# main.net
KiCad netlist of a schematic drawn in EAGLE
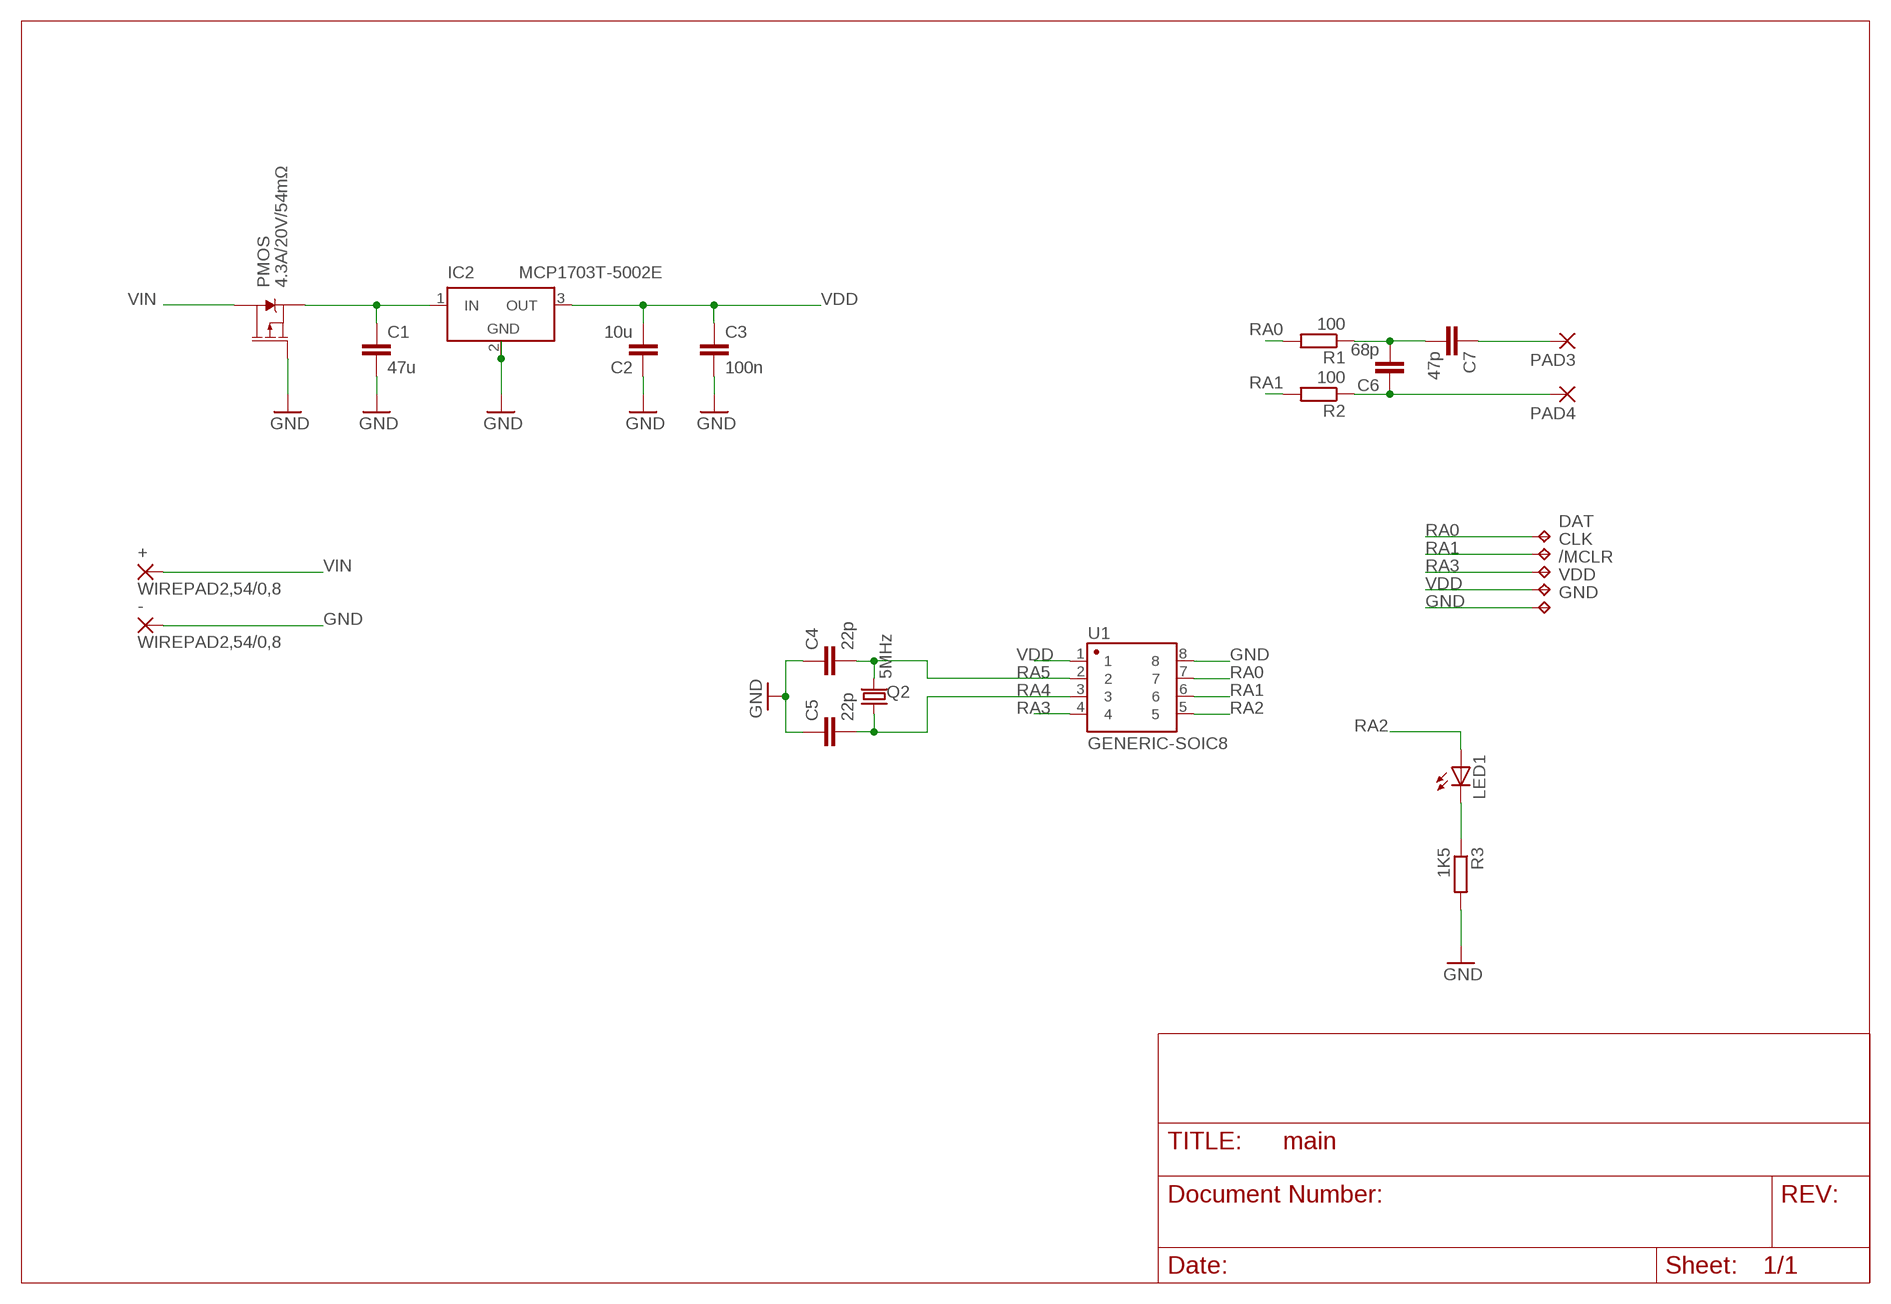
[diagram p0: schematic, sheet 1]

(export (version "E")
  (design (tool "Eeschema 10.0.6"))
  (components
    (comp (ref "+")
      (value "WIREPAD2,54/0,8")
      (footprint "eagle-import:2,54_0,8")
      (libsource (lib "eagle-import") (part "WIREPAD2,54/0,8"))
    )
    (comp (ref "-")
      (value "WIREPAD2,54/0,8")
      (footprint "eagle-import:2,54_0,8")
      (libsource (lib "eagle-import") (part "WIREPAD2,54/0,8"))
    )
    (comp (ref "/MCLR")
      (value "TPTP08SQ")
      (footprint "eagle-import:TP08SQ")
      (libsource (lib "eagle-import") (part "TPTP08SQ"))
    )
    (comp (ref "C1")
      (value "47u")
      (footprint "eagle-import:C1206")
      (libsource (lib "eagle-import") (part "C-EUC1206"))
    )
    (comp (ref "C2")
      (value "10u")
      (footprint "eagle-import:C1206")
      (libsource (lib "eagle-import") (part "C-EUC1206"))
    )
    (comp (ref "C3")
      (value "100n")
      (footprint "eagle-import:C0603")
      (libsource (lib "eagle-import") (part "C-EUC0603"))
    )
    (comp (ref "C4")
      (value "22p")
      (footprint "eagle-import:C0603")
      (libsource (lib "eagle-import") (part "C-EUC0603"))
    )
    (comp (ref "C5")
      (value "22p")
      (footprint "eagle-import:C0603")
      (libsource (lib "eagle-import") (part "C-EUC0603"))
    )
    (comp (ref "C6")
      (value "68p")
      (footprint "eagle-import:C0603")
      (libsource (lib "eagle-import") (part "C-EUC0603"))
    )
    (comp (ref "C7")
      (value "47p")
      (footprint "eagle-import:C0603")
      (libsource (lib "eagle-import") (part "C-EUC0603"))
    )
    (comp (ref "CLK")
      (value "TPTP08SQ")
      (footprint "eagle-import:TP08SQ")
      (libsource (lib "eagle-import") (part "TPTP08SQ"))
    )
    (comp (ref "DAT")
      (value "TPTP08SQ")
      (footprint "eagle-import:TP08SQ")
      (libsource (lib "eagle-import") (part "TPTP08SQ"))
    )
    (comp (ref "GND")
      (value "TPTP08SQ")
      (footprint "eagle-import:TP08SQ")
      (libsource (lib "eagle-import") (part "TPTP08SQ"))
    )
    (comp (ref "IC2")
      (value "MCP1703T-5002E")
      (footprint "eagle-import:SOT223")
      (fields (field (name "MPN") "LT1129CST-5#PBF"))
      (libsource (lib "eagle-import") (part "LT1129CST5"))
    )
    (comp (ref "LED1")
      (value "LEDCHIP-LED0603")
      (footprint "eagle-import:CHIP-LED0603")
      (libsource (lib "eagle-import") (part "LEDCHIP-LED0603"))
    )
    (comp (ref "PAD3")
      (value "1,6/0,9")
      (footprint "eagle-import:1,6_0,9")
      (libsource (lib "eagle-import") (part "1,6/0,9"))
    )
    (comp (ref "PAD4")
      (value "1,6/0,9")
      (footprint "eagle-import:1,6_0,9")
      (libsource (lib "eagle-import") (part "1,6/0,9"))
    )
    (comp (ref "PMOS")
      (value "4.3A/20V/54mΩ")
      (footprint "eagle-import:SOT23-3")
      (libsource (lib "eagle-import") (part "MOSFET_PCH-IRLML2244"))
    )
    (comp (ref "Q2")
      (value "5MHz")
      (footprint "eagle-import:HC49UP")
      (libsource (lib "eagle-import") (part "CRYSTALHC49UP"))
    )
    (comp (ref "R1")
      (value "100")
      (footprint "eagle-import:R0603")
      (libsource (lib "eagle-import") (part "R-EU_R0603"))
    )
    (comp (ref "R2")
      (value "100")
      (footprint "eagle-import:R0603")
      (libsource (lib "eagle-import") (part "R-EU_R0603"))
    )
    (comp (ref "R3")
      (value "1K5")
      (footprint "eagle-import:R0603")
      (libsource (lib "eagle-import") (part "R-EU_R0603"))
    )
    (comp (ref "U1")
      (value "GENERIC-SOIC8")
      (footprint "eagle-import:SO08-UNIVERSAL")
      (libsource (lib "eagle-import") (part "GENERIC-SOIC8"))
    )
    (comp (ref "VDD")
      (value "TPTP08SQ")
      (footprint "eagle-import:TP08SQ")
      (libsource (lib "eagle-import") (part "TPTP08SQ"))
    )
  )
  (nets
    (net (code "1") (name "/RA0") (class "Default")
      (node (ref "DAT") (pin "TP") (pinfunction "TP_TP") (pintype "input"))
      (node (ref "R1") (pin "2") (pinfunction "2_2") (pintype "passive"))
      (node (ref "U1") (pin "7") (pinfunction "7_7") (pintype "bidirectional"))
    )
    (net (code "2") (name "/RA1") (class "Default")
      (node (ref "CLK") (pin "TP") (pinfunction "TP_TP") (pintype "input"))
      (node (ref "R2") (pin "2") (pinfunction "2_2") (pintype "passive"))
      (node (ref "U1") (pin "6") (pinfunction "6_6") (pintype "bidirectional"))
    )
    (net (code "3") (name "/RA2") (class "Default")
      (node (ref "LED1") (pin "A") (pinfunction "A_A") (pintype "passive"))
      (node (ref "U1") (pin "5") (pinfunction "5_5") (pintype "bidirectional"))
    )
    (net (code "4") (name "/RA3") (class "Default")
      (node (ref "/MCLR") (pin "TP") (pinfunction "TP_TP") (pintype "input"))
      (node (ref "U1") (pin "4") (pinfunction "4_4") (pintype "bidirectional"))
    )
    (net (code "5") (name "/RA4") (class "Default")
      (node (ref "C5") (pin "2") (pinfunction "2_2") (pintype "passive"))
      (node (ref "Q2") (pin "1") (pinfunction "1_1") (pintype "passive"))
      (node (ref "U1") (pin "3") (pinfunction "3_3") (pintype "bidirectional"))
    )
    (net (code "6") (name "/RA5") (class "Default")
      (node (ref "C4") (pin "2") (pinfunction "2_2") (pintype "passive"))
      (node (ref "Q2") (pin "2") (pinfunction "2_2") (pintype "passive"))
      (node (ref "U1") (pin "2") (pinfunction "2_2") (pintype "bidirectional"))
    )
    (net (code "7") (name "/VDD") (class "Default")
      (node (ref "C2") (pin "2") (pinfunction "2_2") (pintype "passive"))
      (node (ref "C3") (pin "1") (pinfunction "1_1") (pintype "passive"))
      (node (ref "IC2") (pin "3") (pinfunction "OUT_3") (pintype "output"))
      (node (ref "U1") (pin "1") (pinfunction "1_1") (pintype "bidirectional"))
      (node (ref "VDD") (pin "TP") (pinfunction "TP_TP") (pintype "input"))
    )
    (net (code "8") (name "/VIN") (class "Default")
      (node (ref "+") (pin "1") (pinfunction "P_1") (pintype "passive"))
      (node (ref "PMOS") (pin "3") (pinfunction "D_3") (pintype "bidirectional"))
    )
    (net (code "9") (name "GND") (class "Default")
      (node (ref "-") (pin "1") (pinfunction "P_1") (pintype "passive"))
      (node (ref "C1") (pin "2") (pinfunction "2_2") (pintype "passive"))
      (node (ref "C2") (pin "1") (pinfunction "1_1") (pintype "passive"))
      (node (ref "C3") (pin "2") (pinfunction "2_2") (pintype "passive"))
      (node (ref "C4") (pin "1") (pinfunction "1_1") (pintype "passive"))
      (node (ref "C5") (pin "1") (pinfunction "1_1") (pintype "passive"))
      (node (ref "GND") (pin "TP") (pinfunction "TP_TP") (pintype "input"))
      (node (ref "IC2") (pin "2") (pinfunction "GND_2") (pintype "power_in"))
      (node (ref "PMOS") (pin "1") (pinfunction "G_1") (pintype "bidirectional"))
      (node (ref "R3") (pin "2") (pinfunction "2_2") (pintype "passive"))
      (node (ref "U1") (pin "8") (pinfunction "8_8") (pintype "bidirectional"))
    )
    (net (code "10") (name "Net-(C6-Pad2)") (class "Default")
      (node (ref "C6") (pin "2") (pinfunction "2_2") (pintype "passive"))
      (node (ref "C7") (pin "2") (pinfunction "2_2") (pintype "passive"))
      (node (ref "R1") (pin "1") (pinfunction "1_1") (pintype "passive"))
    )
    (net (code "11") (name "Net-(IC2A-IN)") (class "Default")
      (node (ref "C1") (pin "1") (pinfunction "1_1") (pintype "passive"))
      (node (ref "IC2") (pin "1") (pinfunction "IN_1") (pintype "input"))
      (node (ref "PMOS") (pin "2") (pinfunction "S_2") (pintype "bidirectional"))
    )
    (net (code "12") (name "Net-(LED1-PadC)") (class "Default")
      (node (ref "LED1") (pin "C") (pinfunction "C_C") (pintype "passive"))
      (node (ref "R3") (pin "1") (pinfunction "1_1") (pintype "passive"))
    )
    (net (code "13") (name "Net-(PAD3-P)") (class "Default")
      (node (ref "C7") (pin "1") (pinfunction "1_1") (pintype "passive"))
      (node (ref "PAD3") (pin "1") (pinfunction "P_1") (pintype "passive"))
    )
    (net (code "14") (name "Net-(PAD4-P)") (class "Default")
      (node (ref "C6") (pin "1") (pinfunction "1_1") (pintype "passive"))
      (node (ref "PAD4") (pin "1") (pinfunction "P_1") (pintype "passive"))
      (node (ref "R2") (pin "1") (pinfunction "1_1") (pintype "passive"))
    )
  )
)
